# Blinky.net
KiCad netlist of a schematic drawn in EAGLE
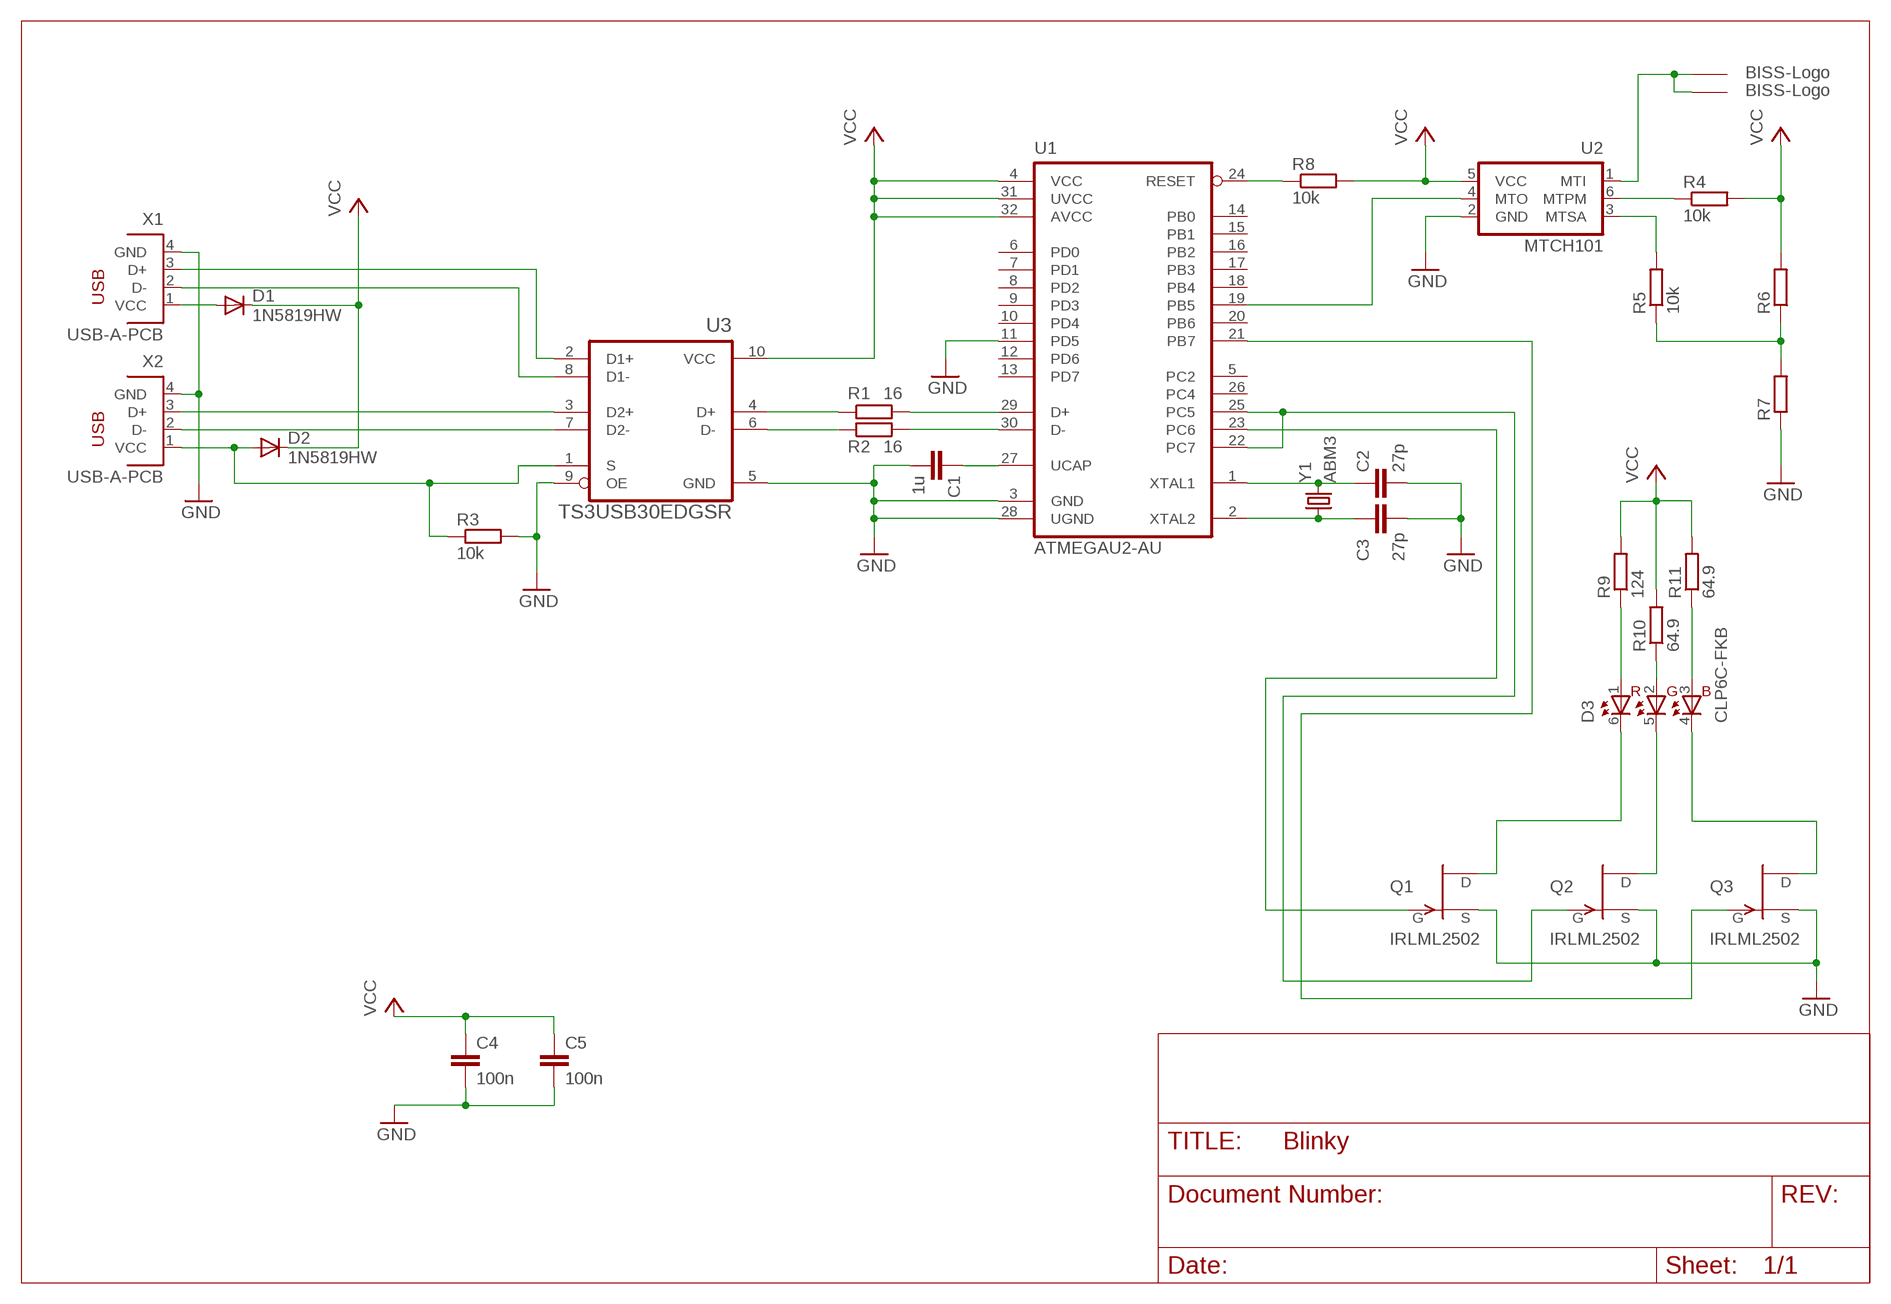
[diagram p0: schematic, sheet 1]

(export (version "E")
  (design (tool "Eeschema 10.0.6"))
  (components
    (comp (ref "C1")
      (value "1u")
      (footprint "eagle-import:C0805")
      (libsource (lib "eagle-import") (part "C-EUC0805"))
    )
    (comp (ref "C2")
      (value "27p")
      (footprint "eagle-import:C0805")
      (libsource (lib "eagle-import") (part "C-EUC0805"))
    )
    (comp (ref "C3")
      (value "27p")
      (footprint "eagle-import:C0805")
      (libsource (lib "eagle-import") (part "C-EUC0805"))
    )
    (comp (ref "C4")
      (value "100n")
      (footprint "eagle-import:C0805")
      (libsource (lib "eagle-import") (part "C-EUC0805"))
    )
    (comp (ref "C5")
      (value "100n")
      (footprint "eagle-import:C0805")
      (libsource (lib "eagle-import") (part "C-EUC0805"))
    )
    (comp (ref "D1")
      (value "1N5819HW")
      (footprint "eagle-import:SOD123")
      (libsource (lib "eagle-import") (part "DIODE-SOD123"))
    )
    (comp (ref "D2")
      (value "1N5819HW")
      (footprint "eagle-import:SOD123")
      (libsource (lib "eagle-import") (part "DIODE-SOD123"))
    )
    (comp (ref "D3")
      (value "CLP6C-FKB")
      (footprint "eagle-import:PLCC-6")
      (libsource (lib "eagle-import") (part "CLP6C-FKB"))
    )
    (comp (ref "Q1")
      (value "IRLML2502")
      (footprint "eagle-import:SOT23")
      (libsource (lib "eagle-import") (part "IRLML2502"))
    )
    (comp (ref "Q2")
      (value "IRLML2502")
      (footprint "eagle-import:SOT23")
      (libsource (lib "eagle-import") (part "IRLML2502"))
    )
    (comp (ref "Q3")
      (value "IRLML2502")
      (footprint "eagle-import:SOT23")
      (libsource (lib "eagle-import") (part "IRLML2502"))
    )
    (comp (ref "R1")
      (value "16")
      (footprint "eagle-import:R0805")
      (libsource (lib "eagle-import") (part "R-EU_R0805"))
    )
    (comp (ref "R2")
      (value "16")
      (footprint "eagle-import:R0805")
      (libsource (lib "eagle-import") (part "R-EU_R0805"))
    )
    (comp (ref "R3")
      (value "10k")
      (footprint "eagle-import:R0805")
      (libsource (lib "eagle-import") (part "R-EU_R0805"))
    )
    (comp (ref "R4")
      (value "10k")
      (footprint "eagle-import:R0805")
      (libsource (lib "eagle-import") (part "R-EU_R0805"))
    )
    (comp (ref "R5")
      (value "10k")
      (footprint "eagle-import:R0805")
      (libsource (lib "eagle-import") (part "R-EU_R0805"))
    )
    (comp (ref "R6")
      (value "R-EU_R0805")
      (footprint "eagle-import:R0805")
      (libsource (lib "eagle-import") (part "R-EU_R0805"))
    )
    (comp (ref "R7")
      (value "R-EU_R0805")
      (footprint "eagle-import:R0805")
      (libsource (lib "eagle-import") (part "R-EU_R0805"))
    )
    (comp (ref "R8")
      (value "10k")
      (footprint "eagle-import:R0805")
      (libsource (lib "eagle-import") (part "R-EU_R0805"))
    )
    (comp (ref "R9")
      (value "124")
      (footprint "eagle-import:R0805")
      (libsource (lib "eagle-import") (part "R-EU_R0805"))
    )
    (comp (ref "R10")
      (value "64.9")
      (footprint "eagle-import:R0805")
      (libsource (lib "eagle-import") (part "R-EU_R0805"))
    )
    (comp (ref "R11")
      (value "64.9")
      (footprint "eagle-import:R0805")
      (libsource (lib "eagle-import") (part "R-EU_R0805"))
    )
    (comp (ref "U$1")
      (value "LOGO")
      (footprint "eagle-import:LOGO")
      (libsource (lib "eagle-import") (part "LOGO"))
    )
    (comp (ref "U$2")
      (value "LOGO")
      (footprint "eagle-import:LOGO")
      (libsource (lib "eagle-import") (part "LOGO"))
    )
    (comp (ref "U1")
      (value "ATMEGAU2-AU")
      (footprint "eagle-import:TQFP32-08")
      (libsource (lib "eagle-import") (part "ATMEGAU2-AU"))
    )
    (comp (ref "U2")
      (value "MTCH101")
      (footprint "eagle-import:SOT23-6")
      (libsource (lib "eagle-import") (part "MTCH101"))
    )
    (comp (ref "U3")
      (value "TS3USB30EDGSR")
      (footprint "eagle-import:VSSOP-10")
      (libsource (lib "eagle-import") (part "TS3USB30EDGSR"))
    )
    (comp (ref "X1")
      (value "USB-A-PCB")
      (footprint "eagle-import:USB-A-PCB")
      (libsource (lib "eagle-import") (part "USB-A-PCB"))
    )
    (comp (ref "X2")
      (value "USB-A-PCB")
      (footprint "eagle-import:USB-A-PCB")
      (libsource (lib "eagle-import") (part "USB-A-PCB"))
    )
    (comp (ref "Y1")
      (value "ABM3")
      (footprint "eagle-import:ABM3")
      (libsource (lib "eagle-import") (part "ABM3"))
    )
  )
  (nets
    (net (code "1") (name "GND") (class "Default")
      (node (ref "C1") (pin "2") (pinfunction "2_2") (pintype "passive"))
      (node (ref "C2") (pin "2") (pinfunction "2_2") (pintype "passive"))
      (node (ref "C3") (pin "2") (pinfunction "2_2") (pintype "passive"))
      (node (ref "C4") (pin "2") (pinfunction "2_2") (pintype "passive"))
      (node (ref "C5") (pin "2") (pinfunction "2_2") (pintype "passive"))
      (node (ref "Q1") (pin "2") (pinfunction "S_2") (pintype "passive"))
      (node (ref "Q2") (pin "2") (pinfunction "S_2") (pintype "passive"))
      (node (ref "Q3") (pin "2") (pinfunction "S_2") (pintype "passive"))
      (node (ref "R3") (pin "2") (pinfunction "2_2") (pintype "passive"))
      (node (ref "R7") (pin "1") (pinfunction "1_1") (pintype "passive"))
      (node (ref "U1") (pin "11") (pinfunction "PD5_11") (pintype "bidirectional"))
      (node (ref "U1") (pin "28") (pinfunction "UGND_28") (pintype "power_in"))
      (node (ref "U1") (pin "3") (pinfunction "GND_3") (pintype "power_in"))
      (node (ref "U2") (pin "2") (pinfunction "GND_2") (pintype "power_in"))
      (node (ref "U3") (pin "5") (pinfunction "GND_5") (pintype "power_in"))
      (node (ref "U3") (pin "9") (pinfunction "OE_9") (pintype "input"))
      (node (ref "X1") (pin "4") (pinfunction "GND_4") (pintype "passive"))
      (node (ref "X2") (pin "4") (pinfunction "GND_4") (pintype "passive"))
    )
    (net (code "2") (name "Net-(D3-Pad1)") (class "Default")
      (node (ref "D3") (pin "1") (pinfunction "1_1") (pintype "passive"))
      (node (ref "R9") (pin "1") (pinfunction "1_1") (pintype "passive"))
    )
    (net (code "3") (name "Net-(D3-Pad2)") (class "Default")
      (node (ref "D3") (pin "2") (pinfunction "2_2") (pintype "passive"))
      (node (ref "R10") (pin "1") (pinfunction "1_1") (pintype "passive"))
    )
    (net (code "4") (name "Net-(D3-Pad3)") (class "Default")
      (node (ref "D3") (pin "3") (pinfunction "3_3") (pintype "passive"))
      (node (ref "R11") (pin "1") (pinfunction "1_1") (pintype "passive"))
    )
    (net (code "5") (name "Net-(Q1-D)") (class "Default")
      (node (ref "D3") (pin "6") (pinfunction "6_6") (pintype "passive"))
      (node (ref "Q1") (pin "3") (pinfunction "D_3") (pintype "passive"))
    )
    (net (code "6") (name "Net-(Q1-G)") (class "Default")
      (node (ref "Q1") (pin "1") (pinfunction "G_1") (pintype "passive"))
      (node (ref "U1") (pin "23") (pinfunction "PC6_23") (pintype "bidirectional"))
    )
    (net (code "7") (name "Net-(Q2-D)") (class "Default")
      (node (ref "D3") (pin "5") (pinfunction "5_5") (pintype "passive"))
      (node (ref "Q2") (pin "3") (pinfunction "D_3") (pintype "passive"))
    )
    (net (code "8") (name "Net-(Q2-G)") (class "Default")
      (node (ref "Q2") (pin "1") (pinfunction "G_1") (pintype "passive"))
      (node (ref "U1") (pin "22") (pinfunction "PC7_22") (pintype "bidirectional"))
      (node (ref "U1") (pin "25") (pinfunction "PC5_25") (pintype "bidirectional"))
    )
    (net (code "9") (name "Net-(Q3-D)") (class "Default")
      (node (ref "D3") (pin "4") (pinfunction "4_4") (pintype "passive"))
      (node (ref "Q3") (pin "3") (pinfunction "D_3") (pintype "passive"))
    )
    (net (code "10") (name "Net-(Q3-G)") (class "Default")
      (node (ref "Q3") (pin "1") (pinfunction "G_1") (pintype "passive"))
      (node (ref "U1") (pin "21") (pinfunction "PB7_21") (pintype "bidirectional"))
    )
    (net (code "11") (name "Net-(R5-Pad1)") (class "Default")
      (node (ref "R5") (pin "1") (pinfunction "1_1") (pintype "passive"))
      (node (ref "R6") (pin "1") (pinfunction "1_1") (pintype "passive"))
      (node (ref "R7") (pin "2") (pinfunction "2_2") (pintype "passive"))
    )
    (net (code "12") (name "Net-(U1-D+)") (class "Default")
      (node (ref "R1") (pin "2") (pinfunction "2_2") (pintype "passive"))
      (node (ref "U1") (pin "29") (pinfunction "D+_29") (pintype "bidirectional"))
    )
    (net (code "13") (name "Net-(U1-D-)") (class "Default")
      (node (ref "R2") (pin "2") (pinfunction "2_2") (pintype "passive"))
      (node (ref "U1") (pin "30") (pinfunction "D-_30") (pintype "bidirectional"))
    )
    (net (code "14") (name "Net-(U1-PB5)") (class "Default")
      (node (ref "U1") (pin "19") (pinfunction "PB5_19") (pintype "bidirectional"))
      (node (ref "U2") (pin "4") (pinfunction "MTO_4") (pintype "open_collector"))
    )
    (net (code "15") (name "Net-(U1-RESET)") (class "Default")
      (node (ref "R8") (pin "1") (pinfunction "1_1") (pintype "passive"))
      (node (ref "U1") (pin "24") (pinfunction "RESET_24") (pintype "input"))
    )
    (net (code "16") (name "Net-(U1-UCAP)") (class "Default")
      (node (ref "C1") (pin "1") (pinfunction "1_1") (pintype "passive"))
      (node (ref "U1") (pin "27") (pinfunction "UCAP_27") (pintype "power_in"))
    )
    (net (code "17") (name "Net-(U1-XTAL1)") (class "Default")
      (node (ref "C2") (pin "1") (pinfunction "1_1") (pintype "passive"))
      (node (ref "U1") (pin "1") (pinfunction "XTAL1_1") (pintype "input"))
      (node (ref "Y1") (pin "2") (pinfunction "2_2") (pintype "passive"))
    )
    (net (code "18") (name "Net-(U1-XTAL2)") (class "Default")
      (node (ref "C3") (pin "1") (pinfunction "1_1") (pintype "passive"))
      (node (ref "U1") (pin "2") (pinfunction "XTAL2_2") (pintype "output"))
      (node (ref "Y1") (pin "1") (pinfunction "1_1") (pintype "passive"))
    )
    (net (code "19") (name "Net-(U2-MTI)") (class "Default")
      (node (ref "U$1") (pin "P$1") (pinfunction "P$1_P$1") (pintype "passive"))
      (node (ref "U$2") (pin "P$1") (pinfunction "P$1_P$1") (pintype "passive"))
      (node (ref "U2") (pin "1") (pinfunction "MTI_1") (pintype "input"))
    )
    (net (code "20") (name "Net-(U2-MTPM)") (class "Default")
      (node (ref "R4") (pin "1") (pinfunction "1_1") (pintype "passive"))
      (node (ref "U2") (pin "6") (pinfunction "MTPM_6") (pintype "input"))
    )
    (net (code "21") (name "Net-(U2-MTSA)") (class "Default")
      (node (ref "R5") (pin "2") (pinfunction "2_2") (pintype "passive"))
      (node (ref "U2") (pin "3") (pinfunction "MTSA_3") (pintype "input"))
    )
    (net (code "22") (name "Net-(U3-D+)") (class "Default")
      (node (ref "R1") (pin "1") (pinfunction "1_1") (pintype "passive"))
      (node (ref "U3") (pin "4") (pinfunction "D+_4") (pintype "bidirectional"))
    )
    (net (code "23") (name "Net-(U3-D-)") (class "Default")
      (node (ref "R2") (pin "1") (pinfunction "1_1") (pintype "passive"))
      (node (ref "U3") (pin "6") (pinfunction "D-_6") (pintype "bidirectional"))
    )
    (net (code "24") (name "Net-(U3-D1+)") (class "Default")
      (node (ref "U3") (pin "2") (pinfunction "D1+_2") (pintype "bidirectional"))
      (node (ref "X1") (pin "3") (pinfunction "D+_3") (pintype "bidirectional"))
    )
    (net (code "25") (name "Net-(U3-D1-)") (class "Default")
      (node (ref "U3") (pin "8") (pinfunction "D1-_8") (pintype "bidirectional"))
      (node (ref "X1") (pin "2") (pinfunction "D-_2") (pintype "bidirectional"))
    )
    (net (code "26") (name "Net-(U3-D2+)") (class "Default")
      (node (ref "U3") (pin "3") (pinfunction "D2+_3") (pintype "bidirectional"))
      (node (ref "X2") (pin "3") (pinfunction "D+_3") (pintype "bidirectional"))
    )
    (net (code "27") (name "Net-(U3-D2-)") (class "Default")
      (node (ref "U3") (pin "7") (pinfunction "D2-_7") (pintype "bidirectional"))
      (node (ref "X2") (pin "2") (pinfunction "D-_2") (pintype "bidirectional"))
    )
    (net (code "28") (name "Net-(U3-S)") (class "Default")
      (node (ref "D2") (pin "A") (pinfunction "A_A") (pintype "passive"))
      (node (ref "R3") (pin "1") (pinfunction "1_1") (pintype "passive"))
      (node (ref "U3") (pin "1") (pinfunction "S_1") (pintype "input"))
      (node (ref "X2") (pin "1") (pinfunction "VCC_1") (pintype "passive"))
    )
    (net (code "29") (name "Net-(X1-VCC)") (class "Default")
      (node (ref "D1") (pin "A") (pinfunction "A_A") (pintype "passive"))
      (node (ref "X1") (pin "1") (pinfunction "VCC_1") (pintype "passive"))
    )
    (net (code "30") (name "VCC") (class "Default")
      (node (ref "C4") (pin "1") (pinfunction "1_1") (pintype "passive"))
      (node (ref "C5") (pin "1") (pinfunction "1_1") (pintype "passive"))
      (node (ref "D1") (pin "C") (pinfunction "C_C") (pintype "passive"))
      (node (ref "D2") (pin "C") (pinfunction "C_C") (pintype "passive"))
      (node (ref "R10") (pin "2") (pinfunction "2_2") (pintype "passive"))
      (node (ref "R11") (pin "2") (pinfunction "2_2") (pintype "passive"))
      (node (ref "R4") (pin "2") (pinfunction "2_2") (pintype "passive"))
      (node (ref "R6") (pin "2") (pinfunction "2_2") (pintype "passive"))
      (node (ref "R8") (pin "2") (pinfunction "2_2") (pintype "passive"))
      (node (ref "R9") (pin "2") (pinfunction "2_2") (pintype "passive"))
      (node (ref "U1") (pin "31") (pinfunction "UVCC_31") (pintype "power_in"))
      (node (ref "U1") (pin "32") (pinfunction "AVCC_32") (pintype "power_in"))
      (node (ref "U1") (pin "4") (pinfunction "VCC_4") (pintype "power_in"))
      (node (ref "U2") (pin "5") (pinfunction "VCC_5") (pintype "power_in"))
      (node (ref "U3") (pin "10") (pinfunction "VCC_10") (pintype "power_in"))
    )
    (net (code "31") (name "unconnected-(U1-PB0-Pad14)") (class "Default")
      (node (ref "U1") (pin "14") (pinfunction "PB0_14") (pintype "bidirectional"))
    )
    (net (code "32") (name "unconnected-(U1-PB1-Pad15)") (class "Default")
      (node (ref "U1") (pin "15") (pinfunction "PB1_15") (pintype "bidirectional"))
    )
    (net (code "33") (name "unconnected-(U1-PB2-Pad16)") (class "Default")
      (node (ref "U1") (pin "16") (pinfunction "PB2_16") (pintype "bidirectional"))
    )
    (net (code "34") (name "unconnected-(U1-PB3-Pad17)") (class "Default")
      (node (ref "U1") (pin "17") (pinfunction "PB3_17") (pintype "bidirectional"))
    )
    (net (code "35") (name "unconnected-(U1-PB4-Pad18)") (class "Default")
      (node (ref "U1") (pin "18") (pinfunction "PB4_18") (pintype "bidirectional"))
    )
    (net (code "36") (name "unconnected-(U1-PB6-Pad20)") (class "Default")
      (node (ref "U1") (pin "20") (pinfunction "PB6_20") (pintype "bidirectional"))
    )
    (net (code "37") (name "unconnected-(U1-PC2-Pad5)") (class "Default")
      (node (ref "U1") (pin "5") (pinfunction "PC2_5") (pintype "bidirectional"))
    )
    (net (code "38") (name "unconnected-(U1-PC4-Pad26)") (class "Default")
      (node (ref "U1") (pin "26") (pinfunction "PC4_26") (pintype "bidirectional"))
    )
    (net (code "39") (name "unconnected-(U1-PD0-Pad6)") (class "Default")
      (node (ref "U1") (pin "6") (pinfunction "PD0_6") (pintype "bidirectional"))
    )
    (net (code "40") (name "unconnected-(U1-PD1-Pad7)") (class "Default")
      (node (ref "U1") (pin "7") (pinfunction "PD1_7") (pintype "bidirectional"))
    )
    (net (code "41") (name "unconnected-(U1-PD2-Pad8)") (class "Default")
      (node (ref "U1") (pin "8") (pinfunction "PD2_8") (pintype "bidirectional"))
    )
    (net (code "42") (name "unconnected-(U1-PD3-Pad9)") (class "Default")
      (node (ref "U1") (pin "9") (pinfunction "PD3_9") (pintype "bidirectional"))
    )
    (net (code "43") (name "unconnected-(U1-PD4-Pad10)") (class "Default")
      (node (ref "U1") (pin "10") (pinfunction "PD4_10") (pintype "bidirectional"))
    )
    (net (code "44") (name "unconnected-(U1-PD6-Pad12)") (class "Default")
      (node (ref "U1") (pin "12") (pinfunction "PD6_12") (pintype "bidirectional"))
    )
    (net (code "45") (name "unconnected-(U1-PD7-Pad13)") (class "Default")
      (node (ref "U1") (pin "13") (pinfunction "PD7_13") (pintype "bidirectional"))
    )
  )
)
